# bbotsv3.net
KiCad netlist of a schematic drawn in EAGLE
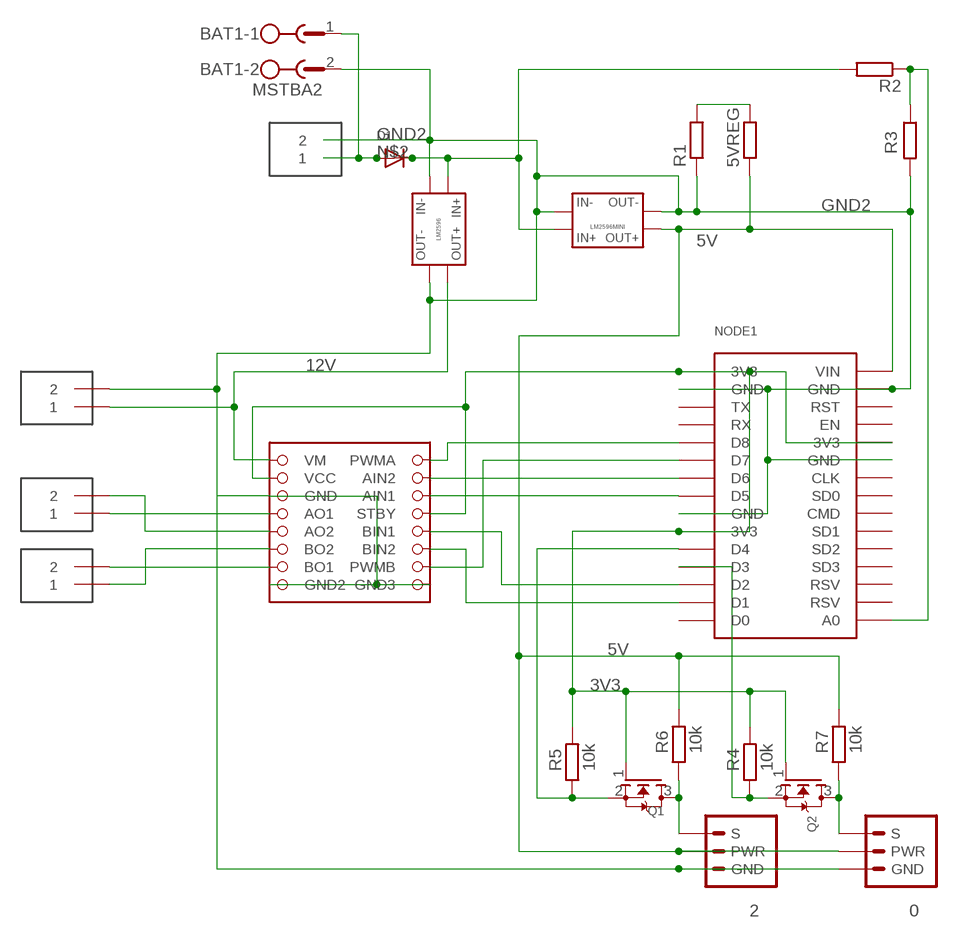
[diagram p0: schematic, sheet 1]

(export (version "E")
  (design (tool "Eeschema 10.0.6"))
  (components
    (comp (ref "0")
      (value "BB-PIN3BB-PIN3")
      (footprint "eagle-import:1X03")
      (libsource (lib "eagle-import") (part "BB-PIN3BB-PIN3"))
    )
    (comp (ref "2")
      (value "BB-PIN3BB-PIN3")
      (footprint "eagle-import:1X03")
      (libsource (lib "eagle-import") (part "BB-PIN3BB-PIN3"))
    )
    (comp (ref "5VREG")
      (value "BB-R0805")
      (footprint "eagle-import:R0805")
      (libsource (lib "eagle-import") (part "BB-R0805"))
    )
    (comp (ref "ARMA")
      (value "TERMINAL_2P")
      (footprint "eagle-import:KF301-2P")
      (libsource (lib "eagle-import") (part "TERMINAL_2P"))
    )
    (comp (ref "ARMA1")
      (value "TERMINAL_2P")
      (footprint "eagle-import:KF301-2P")
      (libsource (lib "eagle-import") (part "TERMINAL_2P"))
    )
    (comp (ref "ARMA2")
      (value "TERMINAL_2P")
      (footprint "eagle-import:KF301-2P")
      (libsource (lib "eagle-import") (part "TERMINAL_2P"))
    )
    (comp (ref "ARMA3")
      (value "TERMINAL_2P")
      (footprint "eagle-import:KF301-2P")
      (libsource (lib "eagle-import") (part "TERMINAL_2P"))
    )
    (comp (ref "BAT1")
      (value "MSTBA2")
      (footprint "eagle-import:MSTBA2")
      (fields (field (name "MF") "FARNELL") (field (name "MPN") "1757242"))
      (libsource (lib "eagle-import") (part "MSTBA2"))
    )
    (comp (ref "D1")
      (value "DIODEDO-1N4148")
      (footprint "eagle-import:DO-1N4148")
      (libsource (lib "eagle-import") (part "DIODEDO-1N4148"))
    )
    (comp (ref "NODE1")
      (value "NODEMCU_ESP8266")
      (footprint "eagle-import:NODEMCU_ESP8266")
      (libsource (lib "eagle-import") (part "NODEMCU_ESP8266"))
    )
    (comp (ref "Q1")
      (value "MOSFET-NWAVE")
      (footprint "eagle-import:SOT23-W")
      (libsource (lib "eagle-import") (part "MOSFET-NWAVE"))
    )
    (comp (ref "Q2")
      (value "MOSFET-NWAVE")
      (footprint "eagle-import:SOT23-W")
      (libsource (lib "eagle-import") (part "MOSFET-NWAVE"))
    )
    (comp (ref "R1")
      (value "100")
      (footprint "eagle-import:R1206")
      (libsource (lib "eagle-import") (part "BB-R1205"))
    )
    (comp (ref "R2")
      (value "10k")
      (footprint "eagle-import:R1206")
      (libsource (lib "eagle-import") (part "BB-R1205"))
    )
    (comp (ref "R3")
      (value "1k")
      (footprint "eagle-import:R1206")
      (libsource (lib "eagle-import") (part "BB-R1205"))
    )
    (comp (ref "R4")
      (value "10k")
      (footprint "eagle-import:R1206")
      (libsource (lib "eagle-import") (part "BB-R1205"))
    )
    (comp (ref "R5")
      (value "10k")
      (footprint "eagle-import:R1206")
      (libsource (lib "eagle-import") (part "BB-R1205"))
    )
    (comp (ref "R6")
      (value "10k")
      (footprint "eagle-import:R1206")
      (libsource (lib "eagle-import") (part "BB-R1205"))
    )
    (comp (ref "R7")
      (value "10k")
      (footprint "eagle-import:R1206")
      (libsource (lib "eagle-import") (part "BB-R1205"))
    )
    (comp (ref "U$1")
      (value "BB-LM2596")
      (footprint "eagle-import:BB-LM2596")
      (libsource (lib "eagle-import") (part "BB-LM2596"))
    )
    (comp (ref "U$2")
      (value "BB-TB6612")
      (footprint "eagle-import:BB-TB6612")
      (libsource (lib "eagle-import") (part "BB-TB6612"))
    )
    (comp (ref "U$3")
      (value "BB-LM2596MINILM2596MINIV2")
      (footprint "eagle-import:LM2596MINIV2")
      (libsource (lib "eagle-import") (part "BB-LM2596MINILM2596MINIV2"))
    )
  )
  (nets
    (net (code "1") (name "/3V3") (class "Default")
      (node (ref "NODE1") (pin "3V3@1") (pinfunction "3V3_3V3@1") (pintype "power_in"))
      (node (ref "NODE1") (pin "3V3@2") (pinfunction "3V3_3V3@2") (pintype "power_in"))
      (node (ref "NODE1") (pin "3V3@3") (pinfunction "3V3_3V3@3") (pintype "power_in"))
      (node (ref "Q1") (pin "1") (pinfunction "G_1") (pintype "bidirectional"))
      (node (ref "Q2") (pin "1") (pinfunction "G_1") (pintype "bidirectional"))
      (node (ref "R4") (pin "2") (pinfunction "2_2") (pintype "passive"))
      (node (ref "R5") (pin "2") (pinfunction "2_2") (pintype "passive"))
      (node (ref "U$2") (pin "STBY") (pinfunction "STBY_STBY") (pintype "bidirectional"))
      (node (ref "U$2") (pin "VCC") (pinfunction "VCC_VCC") (pintype "bidirectional"))
    )
    (net (code "2") (name "/5V") (class "Default")
      (node (ref "0") (pin "P") (pinfunction "PWR_P") (pintype "bidirectional"))
      (node (ref "2") (pin "P") (pinfunction "PWR_P") (pintype "bidirectional"))
      (node (ref "5VREG") (pin "1") (pinfunction "1_1") (pintype "passive"))
      (node (ref "NODE1") (pin "VIN") (pinfunction "VIN_VIN") (pintype "power_in"))
      (node (ref "R6") (pin "2") (pinfunction "2_2") (pintype "passive"))
      (node (ref "R7") (pin "2") (pinfunction "2_2") (pintype "passive"))
      (node (ref "U$3") (pin "OUT+") (pinfunction "OUT+_OUT+") (pintype "bidirectional"))
    )
    (net (code "3") (name "/12V") (class "Default")
      (node (ref "ARMA") (pin "1") (pinfunction "1_1") (pintype "bidirectional"))
      (node (ref "U$1") (pin "OUT+") (pinfunction "OUT+_OUT+") (pintype "bidirectional"))
      (node (ref "U$2") (pin "VM") (pinfunction "VM_VM") (pintype "bidirectional"))
    )
    (net (code "4") (name "/GND2") (class "Default")
      (node (ref "0") (pin "GND") (pinfunction "GND_GND") (pintype "bidirectional"))
      (node (ref "2") (pin "GND") (pinfunction "GND_GND") (pintype "bidirectional"))
      (node (ref "ARMA") (pin "2") (pinfunction "2_2") (pintype "bidirectional"))
      (node (ref "ARMA3") (pin "2") (pinfunction "2_2") (pintype "bidirectional"))
      (node (ref "BAT1") (pin "2") (pinfunction "1_2") (pintype "passive"))
      (node (ref "NODE1") (pin "GND@1") (pinfunction "GND_GND@1") (pintype "power_in"))
      (node (ref "NODE1") (pin "GND@2") (pinfunction "GND_GND@2") (pintype "power_in"))
      (node (ref "NODE1") (pin "GND@3") (pinfunction "GND_GND@3") (pintype "power_in"))
      (node (ref "NODE1") (pin "GND@4") (pinfunction "GND_GND@4") (pintype "power_in"))
      (node (ref "R1") (pin "1") (pinfunction "1_1") (pintype "passive"))
      (node (ref "R3") (pin "2") (pinfunction "2_2") (pintype "passive"))
      (node (ref "U$1") (pin "IN-") (pinfunction "IN-_IN-") (pintype "bidirectional"))
      (node (ref "U$1") (pin "OUT-") (pinfunction "OUT-_OUT-") (pintype "bidirectional"))
      (node (ref "U$2") (pin "GND") (pinfunction "GND_GND") (pintype "bidirectional"))
      (node (ref "U$2") (pin "GND2") (pinfunction "GND2_GND2") (pintype "bidirectional"))
      (node (ref "U$2") (pin "GND3") (pinfunction "GND3_GND3") (pintype "bidirectional"))
      (node (ref "U$3") (pin "IN-") (pinfunction "IN-_IN-") (pintype "bidirectional"))
      (node (ref "U$3") (pin "OUT-") (pinfunction "OUT-_OUT-") (pintype "bidirectional"))
    )
    (net (code "5") (name "/N$2") (class "Default")
      (node (ref "ARMA3") (pin "1") (pinfunction "1_1") (pintype "bidirectional"))
      (node (ref "BAT1") (pin "1") (pinfunction "1_1") (pintype "passive"))
      (node (ref "D1") (pin "A") (pinfunction "A_A") (pintype "passive"))
    )
    (net (code "6") (name "Net-(5VREG-Pad2)") (class "Default")
      (node (ref "5VREG") (pin "2") (pinfunction "2_2") (pintype "passive"))
      (node (ref "R1") (pin "2") (pinfunction "2_2") (pintype "passive"))
    )
    (net (code "7") (name "Net-(ARMA1-Pad1)") (class "Default")
      (node (ref "ARMA1") (pin "1") (pinfunction "1_1") (pintype "bidirectional"))
      (node (ref "U$2") (pin "AO1") (pinfunction "AO1_AO1") (pintype "bidirectional"))
    )
    (net (code "8") (name "Net-(ARMA1-Pad2)") (class "Default")
      (node (ref "ARMA1") (pin "2") (pinfunction "2_2") (pintype "bidirectional"))
      (node (ref "U$2") (pin "AO2") (pinfunction "AO2_AO2") (pintype "bidirectional"))
    )
    (net (code "9") (name "Net-(ARMA2-Pad1)") (class "Default")
      (node (ref "ARMA2") (pin "1") (pinfunction "1_1") (pintype "bidirectional"))
      (node (ref "U$2") (pin "BO2") (pinfunction "BO2_BO2") (pintype "bidirectional"))
    )
    (net (code "10") (name "Net-(ARMA2-Pad2)") (class "Default")
      (node (ref "ARMA2") (pin "2") (pinfunction "2_2") (pintype "bidirectional"))
      (node (ref "U$2") (pin "BO1") (pinfunction "BO1_BO1") (pintype "bidirectional"))
    )
    (net (code "11") (name "Net-(D1-PadC)") (class "Default")
      (node (ref "D1") (pin "C") (pinfunction "C_C") (pintype "passive"))
      (node (ref "R2") (pin "2") (pinfunction "2_2") (pintype "passive"))
      (node (ref "U$1") (pin "IN+") (pinfunction "IN+_IN+") (pintype "bidirectional"))
      (node (ref "U$3") (pin "IN+") (pinfunction "IN+_IN+") (pintype "bidirectional"))
    )
    (net (code "12") (name "Net-(NODE1-PadA0)") (class "Default")
      (node (ref "NODE1") (pin "A0") (pinfunction "A0_A0") (pintype "bidirectional"))
      (node (ref "R2") (pin "1") (pinfunction "1_1") (pintype "passive"))
      (node (ref "R3") (pin "1") (pinfunction "1_1") (pintype "passive"))
    )
    (net (code "13") (name "Net-(NODE1-PadD7)") (class "Default")
      (node (ref "NODE1") (pin "D7") (pinfunction "D7_D7") (pintype "bidirectional"))
      (node (ref "U$2") (pin "PWMB") (pinfunction "PWMB_PWMB") (pintype "bidirectional"))
    )
    (net (code "14") (name "Net-(NODE1-PadD8)") (class "Default")
      (node (ref "NODE1") (pin "D8") (pinfunction "D8_D8") (pintype "bidirectional"))
      (node (ref "U$2") (pin "PWMA") (pinfunction "PWMA_PWMA") (pintype "bidirectional"))
    )
    (net (code "15") (name "Net-(Q1-D)") (class "Default")
      (node (ref "2") (pin "S") (pinfunction "S_S") (pintype "bidirectional"))
      (node (ref "Q1") (pin "3") (pinfunction "D_3") (pintype "bidirectional"))
      (node (ref "R6") (pin "1") (pinfunction "1_1") (pintype "passive"))
    )
    (net (code "16") (name "Net-(Q1-S)") (class "Default")
      (node (ref "NODE1") (pin "D4") (pinfunction "D4_D4") (pintype "bidirectional"))
      (node (ref "Q1") (pin "2") (pinfunction "S_2") (pintype "bidirectional"))
      (node (ref "R5") (pin "1") (pinfunction "1_1") (pintype "passive"))
    )
    (net (code "17") (name "Net-(Q2-D)") (class "Default")
      (node (ref "0") (pin "S") (pinfunction "S_S") (pintype "bidirectional"))
      (node (ref "Q2") (pin "3") (pinfunction "D_3") (pintype "bidirectional"))
      (node (ref "R7") (pin "1") (pinfunction "1_1") (pintype "passive"))
    )
    (net (code "18") (name "Net-(Q2-S)") (class "Default")
      (node (ref "NODE1") (pin "D3") (pinfunction "D3_D3") (pintype "bidirectional"))
      (node (ref "Q2") (pin "2") (pinfunction "S_2") (pintype "bidirectional"))
      (node (ref "R4") (pin "1") (pinfunction "1_1") (pintype "passive"))
    )
    (net (code "19") (name "Net-(U$2-AIN1)") (class "Default")
      (node (ref "NODE1") (pin "D5") (pinfunction "D5_D5") (pintype "bidirectional"))
      (node (ref "U$2") (pin "AI1") (pinfunction "AIN1_AI1") (pintype "bidirectional"))
    )
    (net (code "20") (name "Net-(U$2-AIN2)") (class "Default")
      (node (ref "NODE1") (pin "D6") (pinfunction "D6_D6") (pintype "bidirectional"))
      (node (ref "U$2") (pin "AI2") (pinfunction "AIN2_AI2") (pintype "bidirectional"))
    )
    (net (code "21") (name "Net-(U$2-BIN1)") (class "Default")
      (node (ref "NODE1") (pin "D2") (pinfunction "D2_D2") (pintype "bidirectional"))
      (node (ref "U$2") (pin "BI1") (pinfunction "BIN1_BI1") (pintype "bidirectional"))
    )
    (net (code "22") (name "Net-(U$2-BIN2)") (class "Default")
      (node (ref "NODE1") (pin "D1") (pinfunction "D1_D1") (pintype "bidirectional"))
      (node (ref "U$2") (pin "BI2") (pinfunction "BIN2_BI2") (pintype "bidirectional"))
    )
    (net (code "23") (name "unconnected-(NODE1-PadCLK)") (class "Default")
      (node (ref "NODE1") (pin "CLK") (pinfunction "CLK_CLK") (pintype "bidirectional"))
    )
    (net (code "24") (name "unconnected-(NODE1-PadCMD)") (class "Default")
      (node (ref "NODE1") (pin "CMD") (pinfunction "CMD_CMD") (pintype "bidirectional"))
    )
    (net (code "25") (name "unconnected-(NODE1-PadD0)") (class "Default")
      (node (ref "NODE1") (pin "D0") (pinfunction "D0_D0") (pintype "bidirectional"))
    )
    (net (code "26") (name "unconnected-(NODE1-PadEN)") (class "Default")
      (node (ref "NODE1") (pin "EN") (pinfunction "EN_EN") (pintype "bidirectional"))
    )
    (net (code "27") (name "unconnected-(NODE1-PadRST)") (class "Default")
      (node (ref "NODE1") (pin "RST") (pinfunction "RST_RST") (pintype "bidirectional"))
    )
    (net (code "28") (name "unconnected-(NODE1-PadRX)") (class "Default")
      (node (ref "NODE1") (pin "RX") (pinfunction "RX_RX") (pintype "bidirectional"))
    )
    (net (code "29") (name "unconnected-(NODE1-PadSD1)") (class "Default")
      (node (ref "NODE1") (pin "SD1") (pinfunction "SD1_SD1") (pintype "bidirectional"))
    )
    (net (code "30") (name "unconnected-(NODE1-PadSD2)") (class "Default")
      (node (ref "NODE1") (pin "SD2") (pinfunction "SD2_SD2") (pintype "bidirectional"))
    )
    (net (code "31") (name "unconnected-(NODE1-PadSD3)") (class "Default")
      (node (ref "NODE1") (pin "SD3") (pinfunction "SD3_SD3") (pintype "bidirectional"))
    )
    (net (code "32") (name "unconnected-(NODE1-PadTX)") (class "Default")
      (node (ref "NODE1") (pin "TX") (pinfunction "TX_TX") (pintype "bidirectional"))
    )
    (net (code "33") (name "unconnected-(NODE1-RSV-PadRSV1)") (class "Default")
      (node (ref "NODE1") (pin "RSV1") (pinfunction "RSV_RSV1") (pintype "bidirectional"))
    )
    (net (code "34") (name "unconnected-(NODE1-RSV-PadRSV2)") (class "Default")
      (node (ref "NODE1") (pin "RSV2") (pinfunction "RSV_RSV2") (pintype "bidirectional"))
    )
    (net (code "35") (name "unconnected-(NODE1-SD0-PadSDO)") (class "Default")
      (node (ref "NODE1") (pin "SDO") (pinfunction "SD0_SDO") (pintype "bidirectional"))
    )
  )
)
